# ww101board.net
KiCad netlist of a schematic drawn in EAGLE
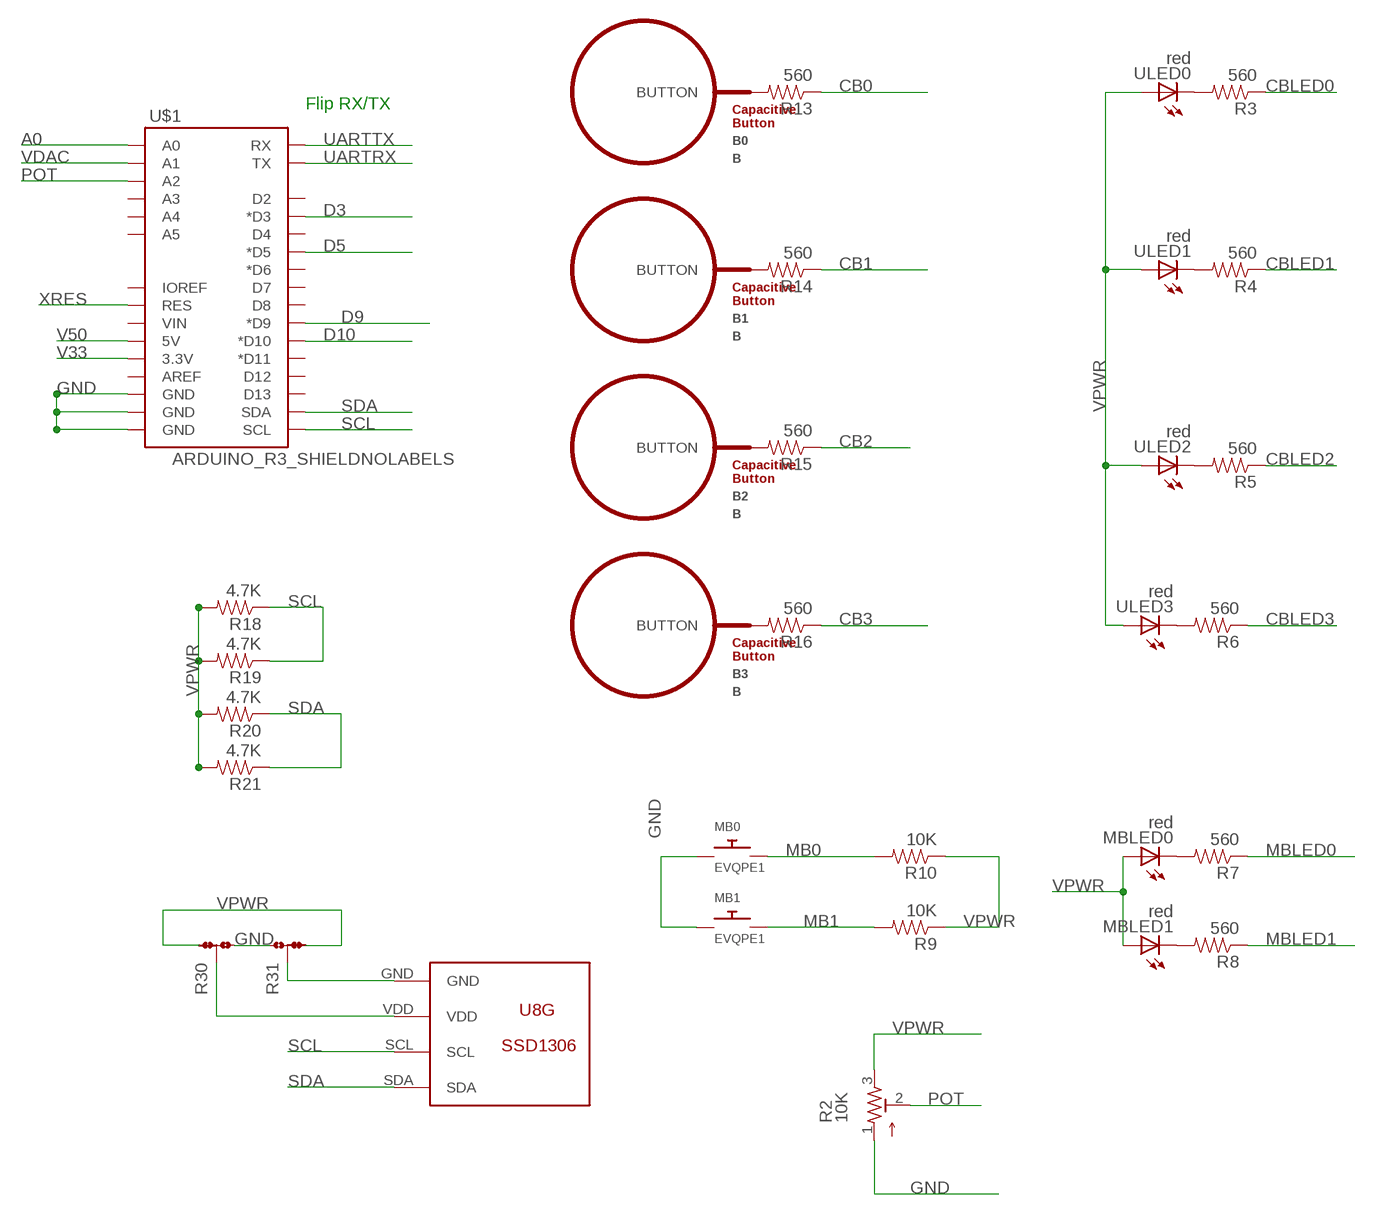
[diagram p0: schematic, sheet 1]
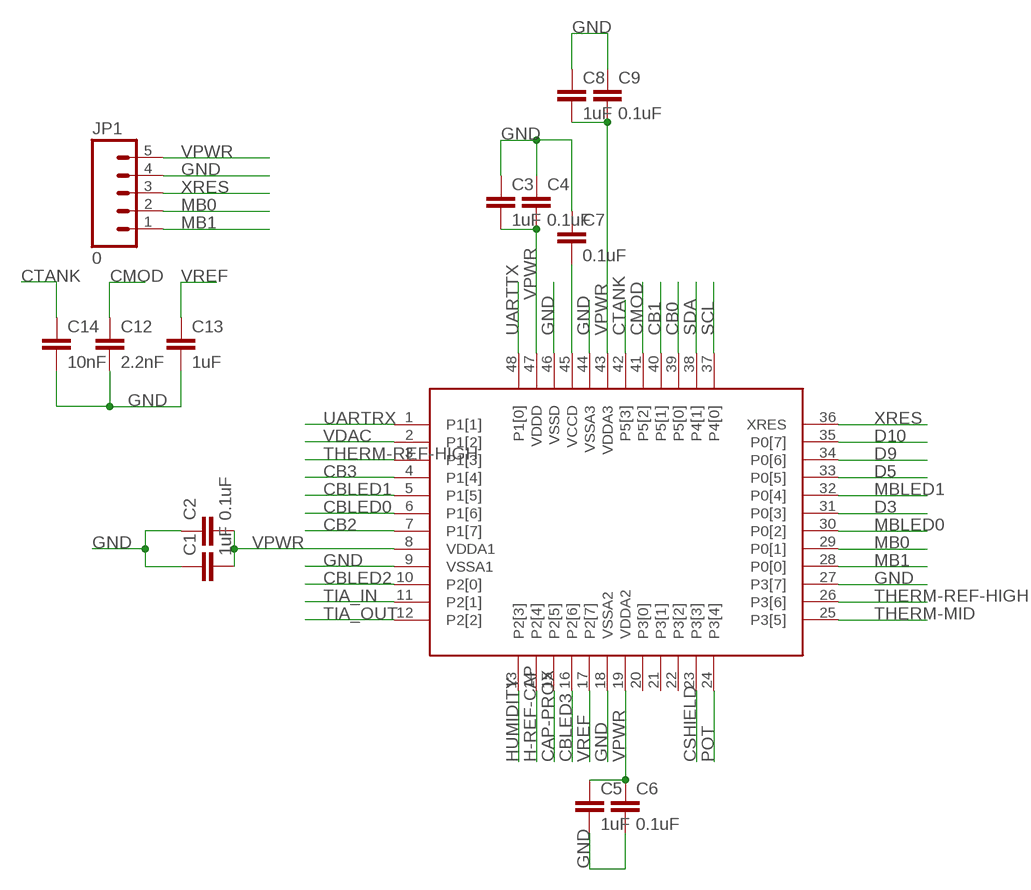
[diagram p1: schematic, sheet 2]
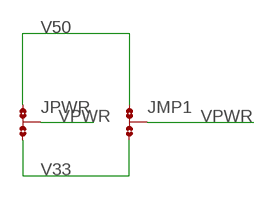
[diagram p2: schematic, sheet 3]
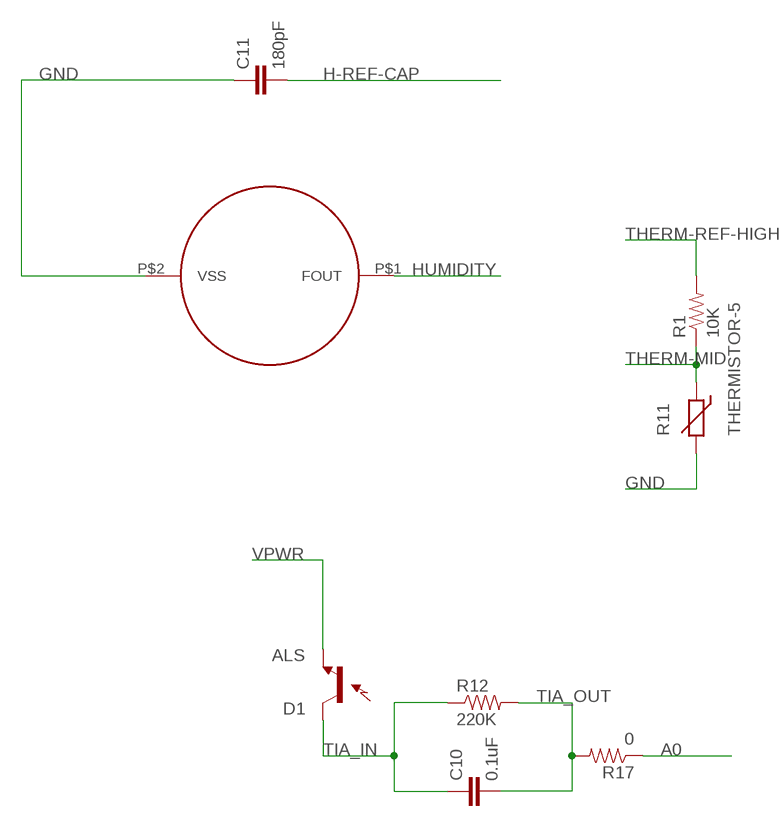
[diagram p3: schematic, sheet 4]

(export (version "E")
  (design (tool "Eeschema 10.0.6"))
  (components
    (comp (ref "B0")
      (value "B")
      (footprint "eagle-import:BUTTON_PASSIVE_10MM")
      (libsource (lib "eagle-import") (part "BUTTON_PASSIVE10MM"))
    )
    (comp (ref "B1")
      (value "B")
      (footprint "eagle-import:BUTTON_PASSIVE_10MM")
      (libsource (lib "eagle-import") (part "BUTTON_PASSIVE10MM"))
    )
    (comp (ref "B2")
      (value "B")
      (footprint "eagle-import:BUTTON_PASSIVE_10MM")
      (libsource (lib "eagle-import") (part "BUTTON_PASSIVE10MM"))
    )
    (comp (ref "B3")
      (value "B")
      (footprint "eagle-import:BUTTON_PASSIVE_10MM")
      (libsource (lib "eagle-import") (part "BUTTON_PASSIVE10MM"))
    )
    (comp (ref "MB0")
      (value "EVQPE1")
      (footprint "eagle-import:SWITCH")
      (libsource (lib "eagle-import") (part "EVQPE1"))
    )
    (comp (ref "MB1")
      (value "EVQPE1")
      (footprint "eagle-import:SWITCH")
      (libsource (lib "eagle-import") (part "EVQPE1"))
    )
    (comp (ref "MBLED0")
      (value "red")
      (footprint "eagle-import:CHIP-LED0603")
      (libsource (lib "eagle-import") (part "LEDCHIP-LED0603"))
    )
    (comp (ref "MBLED1")
      (value "red")
      (footprint "eagle-import:CHIP-LED0603")
      (libsource (lib "eagle-import") (part "LEDCHIP-LED0603"))
    )
    (comp (ref "R2")
      (value "10K")
      (footprint "eagle-import:3386P")
      (libsource (lib "eagle-import") (part "TRIM_US-3386P"))
    )
    (comp (ref "R3")
      (value "560")
      (footprint "eagle-import:0603-RES")
      (libsource (lib "eagle-import") (part "RESISTOR0603"))
    )
    (comp (ref "R4")
      (value "560")
      (footprint "eagle-import:0603-RES")
      (libsource (lib "eagle-import") (part "RESISTOR0603"))
    )
    (comp (ref "R5")
      (value "560")
      (footprint "eagle-import:0603-RES")
      (libsource (lib "eagle-import") (part "RESISTOR0603"))
    )
    (comp (ref "R6")
      (value "560")
      (footprint "eagle-import:0603-RES")
      (libsource (lib "eagle-import") (part "RESISTOR0603"))
    )
    (comp (ref "R7")
      (value "560")
      (footprint "eagle-import:0603-RES")
      (libsource (lib "eagle-import") (part "RESISTOR0603"))
    )
    (comp (ref "R8")
      (value "560")
      (footprint "eagle-import:0603-RES")
      (libsource (lib "eagle-import") (part "RESISTOR0603"))
    )
    (comp (ref "R9")
      (value "10K")
      (footprint "eagle-import:0603-RES")
      (libsource (lib "eagle-import") (part "RESISTOR0603"))
    )
    (comp (ref "R10")
      (value "10K")
      (footprint "eagle-import:0603-RES")
      (libsource (lib "eagle-import") (part "RESISTOR0603"))
    )
    (comp (ref "R13")
      (value "560")
      (footprint "eagle-import:0603-RES")
      (libsource (lib "eagle-import") (part "RESISTOR0603"))
    )
    (comp (ref "R14")
      (value "560")
      (footprint "eagle-import:0603-RES")
      (libsource (lib "eagle-import") (part "RESISTOR0603"))
    )
    (comp (ref "R15")
      (value "560")
      (footprint "eagle-import:0603-RES")
      (libsource (lib "eagle-import") (part "RESISTOR0603"))
    )
    (comp (ref "R16")
      (value "560")
      (footprint "eagle-import:0603-RES")
      (libsource (lib "eagle-import") (part "RESISTOR0603"))
    )
    (comp (ref "R18")
      (value "4.7K")
      (footprint "eagle-import:0603-RES")
      (libsource (lib "eagle-import") (part "RESISTOR0603"))
    )
    (comp (ref "R19")
      (value "4.7K")
      (footprint "eagle-import:0603-RES")
      (libsource (lib "eagle-import") (part "RESISTOR0603"))
    )
    (comp (ref "R20")
      (value "4.7K")
      (footprint "eagle-import:0603-RES")
      (libsource (lib "eagle-import") (part "RESISTOR0603"))
    )
    (comp (ref "R21")
      (value "4.7K")
      (footprint "eagle-import:0603-RES")
      (libsource (lib "eagle-import") (part "RESISTOR0603"))
    )
    (comp (ref "R30")
      (value "JMP-3-1_2")
      (footprint "eagle-import:JMP-3-1_2")
      (libsource (lib "eagle-import") (part "JMP-3-1_2"))
    )
    (comp (ref "R31")
      (value "JMP-3-2_3")
      (footprint "eagle-import:JMP-3-2_3")
      (libsource (lib "eagle-import") (part "JMP-3-2_3"))
    )
    (comp (ref "U$1")
      (value "ARDUINO_R3_SHIELDNOLABELS")
      (footprint "eagle-import:UNO_R3_SHIELD_NOLABELS")
      (libsource (lib "eagle-import") (part "ARDUINO_R3_SHIELDNOLABELS"))
    )
    (comp (ref "U$2")
      (value "U8G-096-OLED")
      (footprint "eagle-import:096-SSD1306")
      (libsource (lib "eagle-import") (part "U8G-096-OLED"))
    )
    (comp (ref "ULED0")
      (value "red")
      (footprint "eagle-import:CHIP-LED0603")
      (libsource (lib "eagle-import") (part "LEDCHIP-LED0603"))
    )
    (comp (ref "ULED1")
      (value "red")
      (footprint "eagle-import:CHIP-LED0603")
      (libsource (lib "eagle-import") (part "LEDCHIP-LED0603"))
    )
    (comp (ref "ULED2")
      (value "red")
      (footprint "eagle-import:CHIP-LED0603")
      (libsource (lib "eagle-import") (part "LEDCHIP-LED0603"))
    )
    (comp (ref "ULED3")
      (value "red")
      (footprint "eagle-import:CHIP-LED0603")
      (libsource (lib "eagle-import") (part "LEDCHIP-LED0603"))
    )
    (comp (ref "C1")
      (value "1uF")
      (footprint "eagle-import:0603-CAP")
      (libsource (lib "eagle-import") (part "CAP0603-CAP"))
    )
    (comp (ref "C2")
      (value "0.1uF")
      (footprint "eagle-import:0603-CAP")
      (libsource (lib "eagle-import") (part "CAP0603-CAP"))
    )
    (comp (ref "C3")
      (value "1uF")
      (footprint "eagle-import:0603-CAP")
      (libsource (lib "eagle-import") (part "CAP0603-CAP"))
    )
    (comp (ref "C4")
      (value "0.1uF")
      (footprint "eagle-import:0603-CAP")
      (libsource (lib "eagle-import") (part "CAP0603-CAP"))
    )
    (comp (ref "C5")
      (value "1uF")
      (footprint "eagle-import:0603-CAP")
      (libsource (lib "eagle-import") (part "CAP0603-CAP"))
    )
    (comp (ref "C6")
      (value "0.1uF")
      (footprint "eagle-import:0603-CAP")
      (libsource (lib "eagle-import") (part "CAP0603-CAP"))
    )
    (comp (ref "C7")
      (value "0.1uF")
      (footprint "eagle-import:0603-CAP")
      (libsource (lib "eagle-import") (part "CAP0603-CAP"))
    )
    (comp (ref "C8")
      (value "1uF")
      (footprint "eagle-import:0603-CAP")
      (libsource (lib "eagle-import") (part "CAP0603-CAP"))
    )
    (comp (ref "C9")
      (value "0.1uF")
      (footprint "eagle-import:0603-CAP")
      (libsource (lib "eagle-import") (part "CAP0603-CAP"))
    )
    (comp (ref "C12")
      (value "2.2nF")
      (footprint "eagle-import:0603-CAP")
      (libsource (lib "eagle-import") (part "CAP0603-CAP"))
    )
    (comp (ref "C13")
      (value "1uF")
      (footprint "eagle-import:0603-CAP")
      (libsource (lib "eagle-import") (part "CAP0603-CAP"))
    )
    (comp (ref "C14")
      (value "10nF")
      (footprint "eagle-import:0603-CAP")
      (libsource (lib "eagle-import") (part "CAP0603-CAP"))
    )
    (comp (ref "JP1")
      (value "0")
      (footprint "eagle-import:1X05_LOCK")
      (libsource (lib "eagle-import") (part "M05LOCK"))
    )
    (comp (ref "U$7")
      (value "CY8C4A45-48")
      (footprint "eagle-import:TQFP-7X7-48")
      (libsource (lib "eagle-import") (part "CY8C4A45-48"))
    )
    (comp (ref "JMP1")
      (value "0")
      (footprint "eagle-import:JMP-3-NO-PTH-2.54")
      (libsource (lib "eagle-import") (part "JMP-3-NO-PTH"))
    )
    (comp (ref "JPWR")
      (value "0")
      (footprint "eagle-import:JMP-3-NO-0603")
      (libsource (lib "eagle-import") (part "JMP-3-NO-0603"))
    )
    (comp (ref "C10")
      (value "0.1uF")
      (footprint "eagle-import:0603-CAP")
      (libsource (lib "eagle-import") (part "CAP0603-CAP"))
    )
    (comp (ref "C11")
      (value "180pF")
      (footprint "eagle-import:0603-CAP")
      (libsource (lib "eagle-import") (part "CAP0603-CAP"))
    )
    (comp (ref "D1")
      (value "ALS")
      (footprint "eagle-import:ALS")
      (libsource (lib "eagle-import") (part "ALS"))
    )
    (comp (ref "HUMIDITY")
      (value "HPP801A031")
      (footprint "eagle-import:HUMIDITY")
      (libsource (lib "eagle-import") (part "HPP801A031"))
    )
    (comp (ref "R1")
      (value "10K")
      (footprint "eagle-import:0603-RES")
      (libsource (lib "eagle-import") (part "RESISTOR0603"))
    )
    (comp (ref "R11")
      (value "THERMISTOR-5")
      (footprint "eagle-import:R-5")
      (libsource (lib "eagle-import") (part "THERMISTOR-5"))
    )
    (comp (ref "R12")
      (value "220K")
      (footprint "eagle-import:0603-RES")
      (libsource (lib "eagle-import") (part "RESISTOR0603"))
    )
    (comp (ref "R17")
      (value "0")
      (footprint "eagle-import:0603-RES")
      (libsource (lib "eagle-import") (part "RESISTOR0603"))
    )
  )
  (nets
    (net (code "1") (name "A0") (class "Default")
      (node (ref "R17") (pin "1") (pinfunction "1_1") (pintype "passive"))
      (node (ref "U$1") (pin "A0") (pinfunction "A0_A0") (pintype "bidirectional"))
    )
    (net (code "2") (name "CAP-PROX") (class "Default")
      (node (ref "U$7") (pin "15") (pinfunction "P2[5]_15") (pintype "bidirectional"))
    )
    (net (code "3") (name "CB0") (class "Default")
      (node (ref "R13") (pin "1") (pinfunction "1_1") (pintype "passive"))
      (node (ref "U$7") (pin "39") (pinfunction "P5[0]_39") (pintype "bidirectional"))
    )
    (net (code "4") (name "CB1") (class "Default")
      (node (ref "R14") (pin "1") (pinfunction "1_1") (pintype "passive"))
      (node (ref "U$7") (pin "40") (pinfunction "P5[1]_40") (pintype "bidirectional"))
    )
    (net (code "5") (name "CB2") (class "Default")
      (node (ref "R15") (pin "1") (pinfunction "1_1") (pintype "passive"))
      (node (ref "U$7") (pin "7") (pinfunction "P1[7]_7") (pintype "bidirectional"))
    )
    (net (code "6") (name "CB3") (class "Default")
      (node (ref "R16") (pin "1") (pinfunction "1_1") (pintype "passive"))
      (node (ref "U$7") (pin "4") (pinfunction "P1[4]_4") (pintype "bidirectional"))
    )
    (net (code "7") (name "CBLED0") (class "Default")
      (node (ref "R3") (pin "1") (pinfunction "1_1") (pintype "passive"))
      (node (ref "U$7") (pin "6") (pinfunction "P1[6]_6") (pintype "bidirectional"))
    )
    (net (code "8") (name "CBLED1") (class "Default")
      (node (ref "R4") (pin "1") (pinfunction "1_1") (pintype "passive"))
      (node (ref "U$7") (pin "5") (pinfunction "P1[5]_5") (pintype "bidirectional"))
    )
    (net (code "9") (name "CBLED2") (class "Default")
      (node (ref "R5") (pin "1") (pinfunction "1_1") (pintype "passive"))
      (node (ref "U$7") (pin "10") (pinfunction "P2[0]_10") (pintype "bidirectional"))
    )
    (net (code "10") (name "CBLED3") (class "Default")
      (node (ref "R6") (pin "1") (pinfunction "1_1") (pintype "passive"))
      (node (ref "U$7") (pin "16") (pinfunction "P2[6]_16") (pintype "bidirectional"))
    )
    (net (code "11") (name "CMOD") (class "Default")
      (node (ref "C12") (pin "1") (pinfunction "1_1") (pintype "passive"))
      (node (ref "U$7") (pin "41") (pinfunction "P5[2]_41") (pintype "bidirectional"))
    )
    (net (code "12") (name "CSHIELD") (class "Default")
      (node (ref "U$7") (pin "23") (pinfunction "P3[3]_23") (pintype "bidirectional"))
    )
    (net (code "13") (name "CTANK") (class "Default")
      (node (ref "C14") (pin "1") (pinfunction "1_1") (pintype "passive"))
      (node (ref "U$7") (pin "42") (pinfunction "P5[3]_42") (pintype "bidirectional"))
    )
    (net (code "14") (name "D3") (class "Default")
      (node (ref "U$1") (pin "D3") (pinfunction "*D3_D3") (pintype "bidirectional"))
      (node (ref "U$7") (pin "31") (pinfunction "P0[3]_31") (pintype "bidirectional"))
    )
    (net (code "15") (name "D5") (class "Default")
      (node (ref "U$1") (pin "D5") (pinfunction "*D5_D5") (pintype "bidirectional"))
      (node (ref "U$7") (pin "33") (pinfunction "P0[5]_33") (pintype "bidirectional"))
    )
    (net (code "16") (name "D9") (class "Default")
      (node (ref "U$1") (pin "D9") (pinfunction "*D9_D9") (pintype "bidirectional"))
      (node (ref "U$7") (pin "34") (pinfunction "P0[6]_34") (pintype "bidirectional"))
    )
    (net (code "17") (name "D10") (class "Default")
      (node (ref "U$1") (pin "D10") (pinfunction "*D10_D10") (pintype "bidirectional"))
      (node (ref "U$7") (pin "35") (pinfunction "P0[7]_35") (pintype "bidirectional"))
    )
    (net (code "18") (name "GND") (class "Default")
      (node (ref "C1") (pin "1") (pinfunction "1_1") (pintype "passive"))
      (node (ref "C11") (pin "1") (pinfunction "1_1") (pintype "passive"))
      (node (ref "C12") (pin "2") (pinfunction "2_2") (pintype "passive"))
      (node (ref "C13") (pin "2") (pinfunction "2_2") (pintype "passive"))
      (node (ref "C14") (pin "2") (pinfunction "2_2") (pintype "passive"))
      (node (ref "C2") (pin "1") (pinfunction "1_1") (pintype "passive"))
      (node (ref "C3") (pin "1") (pinfunction "1_1") (pintype "passive"))
      (node (ref "C4") (pin "1") (pinfunction "1_1") (pintype "passive"))
      (node (ref "C5") (pin "2") (pinfunction "2_2") (pintype "passive"))
      (node (ref "C6") (pin "2") (pinfunction "2_2") (pintype "passive"))
      (node (ref "C7") (pin "1") (pinfunction "1_1") (pintype "passive"))
      (node (ref "C8") (pin "1") (pinfunction "1_1") (pintype "passive"))
      (node (ref "C9") (pin "1") (pinfunction "1_1") (pintype "passive"))
      (node (ref "HUMIDITY") (pin "P$2") (pinfunction "VSS_P$2") (pintype "bidirectional"))
      (node (ref "JP1") (pin "4") (pinfunction "4_4") (pintype "passive"))
      (node (ref "MB0") (pin "P$1") (pinfunction "P$1_P$1") (pintype "passive"))
      (node (ref "MB1") (pin "P$1") (pinfunction "P$1_P$1") (pintype "passive"))
      (node (ref "R11") (pin "2") (pinfunction "2_2") (pintype "passive"))
      (node (ref "R2") (pin "1") (pinfunction "1_1") (pintype "passive"))
      (node (ref "R30") (pin "3") (pinfunction "3_3") (pintype "passive"))
      (node (ref "R31") (pin "1") (pinfunction "1_1") (pintype "passive"))
      (node (ref "U$1") (pin "GND@0") (pinfunction "GND_GND@0") (pintype "bidirectional"))
      (node (ref "U$1") (pin "GND@1") (pinfunction "GND_GND@1") (pintype "bidirectional"))
      (node (ref "U$1") (pin "GND@2") (pinfunction "GND_GND@2") (pintype "bidirectional"))
      (node (ref "U$7") (pin "18") (pinfunction "VSSA2_18") (pintype "bidirectional"))
      (node (ref "U$7") (pin "27") (pinfunction "P3[7]_27") (pintype "bidirectional"))
      (node (ref "U$7") (pin "44") (pinfunction "VSSA3_44") (pintype "bidirectional"))
      (node (ref "U$7") (pin "46") (pinfunction "VSSD_46") (pintype "bidirectional"))
      (node (ref "U$7") (pin "9") (pinfunction "VSSA1_9") (pintype "bidirectional"))
    )
    (net (code "19") (name "H-REF-CAP") (class "Default")
      (node (ref "C11") (pin "2") (pinfunction "2_2") (pintype "passive"))
      (node (ref "U$7") (pin "14") (pinfunction "P2[4]_14") (pintype "bidirectional"))
    )
    (net (code "20") (name "HUMIDITY") (class "Default")
      (node (ref "HUMIDITY") (pin "P$1") (pinfunction "FOUT_P$1") (pintype "bidirectional"))
      (node (ref "U$7") (pin "13") (pinfunction "P2[3]_13") (pintype "bidirectional"))
    )
    (net (code "21") (name "MB0") (class "Default")
      (node (ref "JP1") (pin "2") (pinfunction "2_2") (pintype "passive"))
      (node (ref "MB0") (pin "P$2") (pinfunction "P$2_P$2") (pintype "passive"))
      (node (ref "R10") (pin "2") (pinfunction "2_2") (pintype "passive"))
      (node (ref "U$7") (pin "29") (pinfunction "P0[1]_29") (pintype "bidirectional"))
    )
    (net (code "22") (name "MB1") (class "Default")
      (node (ref "JP1") (pin "1") (pinfunction "1_1") (pintype "passive"))
      (node (ref "MB1") (pin "P$2") (pinfunction "P$2_P$2") (pintype "passive"))
      (node (ref "R9") (pin "2") (pinfunction "2_2") (pintype "passive"))
      (node (ref "U$7") (pin "28") (pinfunction "P0[0]_28") (pintype "bidirectional"))
    )
    (net (code "23") (name "MBLED0") (class "Default")
      (node (ref "R7") (pin "1") (pinfunction "1_1") (pintype "passive"))
      (node (ref "U$7") (pin "30") (pinfunction "P0[2]_30") (pintype "bidirectional"))
    )
    (net (code "24") (name "MBLED1") (class "Default")
      (node (ref "R8") (pin "1") (pinfunction "1_1") (pintype "passive"))
      (node (ref "U$7") (pin "32") (pinfunction "P0[4]_32") (pintype "bidirectional"))
    )
    (net (code "25") (name "Net-(B0-PadBUTTON)") (class "Default")
      (node (ref "B0") (pin "BUTTON") (pinfunction "BUTTON_BUTTON") (pintype "passive"))
      (node (ref "R13") (pin "2") (pinfunction "2_2") (pintype "passive"))
    )
    (net (code "26") (name "Net-(B1-PadBUTTON)") (class "Default")
      (node (ref "B1") (pin "BUTTON") (pinfunction "BUTTON_BUTTON") (pintype "passive"))
      (node (ref "R14") (pin "2") (pinfunction "2_2") (pintype "passive"))
    )
    (net (code "27") (name "Net-(B2-PadBUTTON)") (class "Default")
      (node (ref "B2") (pin "BUTTON") (pinfunction "BUTTON_BUTTON") (pintype "passive"))
      (node (ref "R15") (pin "2") (pinfunction "2_2") (pintype "passive"))
    )
    (net (code "28") (name "Net-(B3-PadBUTTON)") (class "Default")
      (node (ref "B3") (pin "BUTTON") (pinfunction "BUTTON_BUTTON") (pintype "passive"))
      (node (ref "R16") (pin "2") (pinfunction "2_2") (pintype "passive"))
    )
    (net (code "29") (name "Net-(MBLED0-PadC)") (class "Default")
      (node (ref "MBLED0") (pin "C") (pinfunction "C_C") (pintype "passive"))
      (node (ref "R7") (pin "2") (pinfunction "2_2") (pintype "passive"))
    )
    (net (code "30") (name "Net-(MBLED1-PadC)") (class "Default")
      (node (ref "MBLED1") (pin "C") (pinfunction "C_C") (pintype "passive"))
      (node (ref "R8") (pin "2") (pinfunction "2_2") (pintype "passive"))
    )
    (net (code "31") (name "Net-(R3-Pad2)") (class "Default")
      (node (ref "R3") (pin "2") (pinfunction "2_2") (pintype "passive"))
      (node (ref "ULED0") (pin "C") (pinfunction "C_C") (pintype "passive"))
    )
    (net (code "32") (name "Net-(R4-Pad2)") (class "Default")
      (node (ref "R4") (pin "2") (pinfunction "2_2") (pintype "passive"))
      (node (ref "ULED1") (pin "C") (pinfunction "C_C") (pintype "passive"))
    )
    (net (code "33") (name "Net-(R5-Pad2)") (class "Default")
      (node (ref "R5") (pin "2") (pinfunction "2_2") (pintype "passive"))
      (node (ref "ULED2") (pin "C") (pinfunction "C_C") (pintype "passive"))
    )
    (net (code "34") (name "Net-(R6-Pad2)") (class "Default")
      (node (ref "R6") (pin "2") (pinfunction "2_2") (pintype "passive"))
      (node (ref "ULED3") (pin "C") (pinfunction "C_C") (pintype "passive"))
    )
    (net (code "35") (name "Net-(R30-Pad2)") (class "Default")
      (node (ref "R30") (pin "2") (pinfunction "2_2") (pintype "passive"))
      (node (ref "U$2") (pin "VDD") (pinfunction "VDD_VDD") (pintype "power_in"))
    )
    (net (code "36") (name "Net-(R31-Pad2)") (class "Default")
      (node (ref "R31") (pin "2") (pinfunction "2_2") (pintype "passive"))
      (node (ref "U$2") (pin "GND") (pinfunction "GND_GND") (pintype "power_in"))
    )
    (net (code "37") (name "Net-(U$7-VCCD)") (class "Default")
      (node (ref "C7") (pin "2") (pinfunction "2_2") (pintype "passive"))
      (node (ref "U$7") (pin "45") (pinfunction "VCCD_45") (pintype "bidirectional"))
    )
    (net (code "38") (name "POT") (class "Default")
      (node (ref "R2") (pin "2") (pinfunction "2_2") (pintype "passive"))
      (node (ref "U$1") (pin "A2") (pinfunction "A2_A2") (pintype "bidirectional"))
      (node (ref "U$7") (pin "24") (pinfunction "P3[4]_24") (pintype "bidirectional"))
    )
    (net (code "39") (name "SCL") (class "Default")
      (node (ref "R18") (pin "1") (pinfunction "1_1") (pintype "passive"))
      (node (ref "R19") (pin "1") (pinfunction "1_1") (pintype "passive"))
      (node (ref "U$1") (pin "SCL") (pinfunction "SCL_SCL") (pintype "bidirectional"))
      (node (ref "U$2") (pin "SCL") (pinfunction "SCL_SCL") (pintype "bidirectional"))
      (node (ref "U$7") (pin "37") (pinfunction "P4[0]_37") (pintype "bidirectional"))
    )
    (net (code "40") (name "SDA") (class "Default")
      (node (ref "R20") (pin "1") (pinfunction "1_1") (pintype "passive"))
      (node (ref "R21") (pin "1") (pinfunction "1_1") (pintype "passive"))
      (node (ref "U$1") (pin "SDA") (pinfunction "SDA_SDA") (pintype "bidirectional"))
      (node (ref "U$2") (pin "SDA") (pinfunction "SDA_SDA") (pintype "bidirectional"))
      (node (ref "U$7") (pin "38") (pinfunction "P4[1]_38") (pintype "bidirectional"))
    )
    (net (code "41") (name "THERM-MID") (class "Default")
      (node (ref "R1") (pin "1") (pinfunction "1_1") (pintype "passive"))
      (node (ref "R11") (pin "1") (pinfunction "1_1") (pintype "passive"))
      (node (ref "U$7") (pin "25") (pinfunction "P3[5]_25") (pintype "bidirectional"))
    )
    (net (code "42") (name "THERM-REF-HIGH") (class "Default")
      (node (ref "R1") (pin "2") (pinfunction "2_2") (pintype "passive"))
      (node (ref "U$7") (pin "26") (pinfunction "P3[6]_26") (pintype "bidirectional"))
      (node (ref "U$7") (pin "3") (pinfunction "P1[3]_3") (pintype "bidirectional"))
    )
    (net (code "43") (name "TIA_IN") (class "Default")
      (node (ref "C10") (pin "1") (pinfunction "1_1") (pintype "passive"))
      (node (ref "D1") (pin "CATHODE") (pinfunction "C1_CATHODE") (pintype "passive"))
      (node (ref "R12") (pin "1") (pinfunction "1_1") (pintype "passive"))
      (node (ref "U$7") (pin "11") (pinfunction "P2[1]_11") (pintype "bidirectional"))
    )
    (net (code "44") (name "TIA_OUT") (class "Default")
      (node (ref "C10") (pin "2") (pinfunction "2_2") (pintype "passive"))
      (node (ref "R12") (pin "2") (pinfunction "2_2") (pintype "passive"))
      (node (ref "R17") (pin "2") (pinfunction "2_2") (pintype "passive"))
      (node (ref "U$7") (pin "12") (pinfunction "P2[2]_12") (pintype "bidirectional"))
    )
    (net (code "45") (name "UARTRX") (class "Default")
      (node (ref "U$1") (pin "TX") (pinfunction "TX_TX") (pintype "bidirectional"))
      (node (ref "U$7") (pin "1") (pinfunction "P1[1]_1") (pintype "bidirectional"))
    )
    (net (code "46") (name "UARTTX") (class "Default")
      (node (ref "U$1") (pin "RX") (pinfunction "RX_RX") (pintype "bidirectional"))
      (node (ref "U$7") (pin "48") (pinfunction "P1[0]_48") (pintype "bidirectional"))
    )
    (net (code "47") (name "V33") (class "Default")
      (node (ref "JMP1") (pin "3") (pinfunction "3_3") (pintype "passive"))
      (node (ref "JPWR") (pin "3") (pinfunction "3_3") (pintype "passive"))
      (node (ref "U$1") (pin "3.3V") (pinfunction "3.3V_3.3V") (pintype "bidirectional"))
    )
    (net (code "48") (name "V50") (class "Default")
      (node (ref "JMP1") (pin "1") (pinfunction "1_1") (pintype "passive"))
      (node (ref "JPWR") (pin "1") (pinfunction "1_1") (pintype "passive"))
      (node (ref "U$1") (pin "5V") (pinfunction "5V_5V") (pintype "bidirectional"))
    )
    (net (code "49") (name "VDAC") (class "Default")
      (node (ref "U$1") (pin "A1") (pinfunction "A1_A1") (pintype "bidirectional"))
      (node (ref "U$7") (pin "2") (pinfunction "P1[2]_2") (pintype "bidirectional"))
    )
    (net (code "50") (name "VPWR") (class "Default")
      (node (ref "C1") (pin "2") (pinfunction "2_2") (pintype "passive"))
      (node (ref "C2") (pin "2") (pinfunction "2_2") (pintype "passive"))
      (node (ref "C3") (pin "2") (pinfunction "2_2") (pintype "passive"))
      (node (ref "C4") (pin "2") (pinfunction "2_2") (pintype "passive"))
      (node (ref "C5") (pin "1") (pinfunction "1_1") (pintype "passive"))
      (node (ref "C6") (pin "1") (pinfunction "1_1") (pintype "passive"))
      (node (ref "C8") (pin "2") (pinfunction "2_2") (pintype "passive"))
      (node (ref "C9") (pin "2") (pinfunction "2_2") (pintype "passive"))
      (node (ref "D1") (pin "ANNODE") (pinfunction "E1_ANNODE") (pintype "passive"))
      (node (ref "JMP1") (pin "2") (pinfunction "2_2") (pintype "passive"))
      (node (ref "JP1") (pin "5") (pinfunction "5_5") (pintype "passive"))
      (node (ref "JPWR") (pin "2") (pinfunction "2_2") (pintype "passive"))
      (node (ref "MBLED0") (pin "A") (pinfunction "A_A") (pintype "passive"))
      (node (ref "MBLED1") (pin "A") (pinfunction "A_A") (pintype "passive"))
      (node (ref "R10") (pin "1") (pinfunction "1_1") (pintype "passive"))
      (node (ref "R18") (pin "2") (pinfunction "2_2") (pintype "passive"))
      (node (ref "R19") (pin "2") (pinfunction "2_2") (pintype "passive"))
      (node (ref "R2") (pin "3") (pinfunction "3_3") (pintype "passive"))
      (node (ref "R20") (pin "2") (pinfunction "2_2") (pintype "passive"))
      (node (ref "R21") (pin "2") (pinfunction "2_2") (pintype "passive"))
      (node (ref "R30") (pin "1") (pinfunction "1_1") (pintype "passive"))
      (node (ref "R31") (pin "3") (pinfunction "3_3") (pintype "passive"))
      (node (ref "R9") (pin "1") (pinfunction "1_1") (pintype "passive"))
      (node (ref "U$7") (pin "19") (pinfunction "VDDA2_19") (pintype "bidirectional"))
      (node (ref "U$7") (pin "43") (pinfunction "VDDA3_43") (pintype "bidirectional"))
      (node (ref "U$7") (pin "47") (pinfunction "VDDD_47") (pintype "bidirectional"))
      (node (ref "U$7") (pin "8") (pinfunction "VDDA1_8") (pintype "bidirectional"))
      (node (ref "ULED0") (pin "A") (pinfunction "A_A") (pintype "passive"))
      (node (ref "ULED1") (pin "A") (pinfunction "A_A") (pintype "passive"))
      (node (ref "ULED2") (pin "A") (pinfunction "A_A") (pintype "passive"))
      (node (ref "ULED3") (pin "A") (pinfunction "A_A") (pintype "passive"))
    )
    (net (code "51") (name "VREF") (class "Default")
      (node (ref "C13") (pin "1") (pinfunction "1_1") (pintype "passive"))
      (node (ref "U$7") (pin "17") (pinfunction "P2[7]_17") (pintype "bidirectional"))
    )
    (net (code "52") (name "XRES") (class "Default")
      (node (ref "JP1") (pin "3") (pinfunction "3_3") (pintype "passive"))
      (node (ref "U$1") (pin "RES") (pinfunction "RES_RES") (pintype "bidirectional"))
      (node (ref "U$7") (pin "36") (pinfunction "XRES_36") (pintype "bidirectional"))
    )
    (net (code "53") (name "unconnected-(U$1-*D6-PadD6)") (class "Default")
      (node (ref "U$1") (pin "D6") (pinfunction "*D6_D6") (pintype "bidirectional"))
    )
    (net (code "54") (name "unconnected-(U$1-*D11-PadD11)") (class "Default")
      (node (ref "U$1") (pin "D11") (pinfunction "*D11_D11") (pintype "bidirectional"))
    )
    (net (code "55") (name "unconnected-(U$1-PadA3)") (class "Default")
      (node (ref "U$1") (pin "A3") (pinfunction "A3_A3") (pintype "bidirectional"))
    )
    (net (code "56") (name "unconnected-(U$1-PadA4)") (class "Default")
      (node (ref "U$1") (pin "A4") (pinfunction "A4_A4") (pintype "bidirectional"))
    )
    (net (code "57") (name "unconnected-(U$1-PadA5)") (class "Default")
      (node (ref "U$1") (pin "A5") (pinfunction "A5_A5") (pintype "bidirectional"))
    )
    (net (code "58") (name "unconnected-(U$1-PadAREF)") (class "Default")
      (node (ref "U$1") (pin "AREF") (pinfunction "AREF_AREF") (pintype "bidirectional"))
    )
    (net (code "59") (name "unconnected-(U$1-PadD2)") (class "Default")
      (node (ref "U$1") (pin "D2") (pinfunction "D2_D2") (pintype "bidirectional"))
    )
    (net (code "60") (name "unconnected-(U$1-PadD4)") (class "Default")
      (node (ref "U$1") (pin "D4") (pinfunction "D4_D4") (pintype "bidirectional"))
    )
    (net (code "61") (name "unconnected-(U$1-PadD7)") (class "Default")
      (node (ref "U$1") (pin "D7") (pinfunction "D7_D7") (pintype "bidirectional"))
    )
    (net (code "62") (name "unconnected-(U$1-PadD8)") (class "Default")
      (node (ref "U$1") (pin "D8") (pinfunction "D8_D8") (pintype "bidirectional"))
    )
    (net (code "63") (name "unconnected-(U$1-PadD12)") (class "Default")
      (node (ref "U$1") (pin "D12") (pinfunction "D12_D12") (pintype "bidirectional"))
    )
    (net (code "64") (name "unconnected-(U$1-PadD13)") (class "Default")
      (node (ref "U$1") (pin "D13") (pinfunction "D13_D13") (pintype "bidirectional"))
    )
    (net (code "65") (name "unconnected-(U$1-PadIOREF)") (class "Default")
      (node (ref "U$1") (pin "IOREF") (pinfunction "IOREF_IOREF") (pintype "bidirectional"))
    )
    (net (code "66") (name "unconnected-(U$1-PadVIN)") (class "Default")
      (node (ref "U$1") (pin "VIN") (pinfunction "VIN_VIN") (pintype "bidirectional"))
    )
    (net (code "67") (name "unconnected-(U$7-P3[0]-Pad20)") (class "Default")
      (node (ref "U$7") (pin "20") (pinfunction "P3[0]_20") (pintype "bidirectional"))
    )
    (net (code "68") (name "unconnected-(U$7-P3[1]-Pad21)") (class "Default")
      (node (ref "U$7") (pin "21") (pinfunction "P3[1]_21") (pintype "bidirectional"))
    )
    (net (code "69") (name "unconnected-(U$7-P3[2]-Pad22)") (class "Default")
      (node (ref "U$7") (pin "22") (pinfunction "P3[2]_22") (pintype "bidirectional"))
    )
  )
)
